# SCH_SPD-NFC.net
KiCad netlist of a schematic drawn in EasyEDA
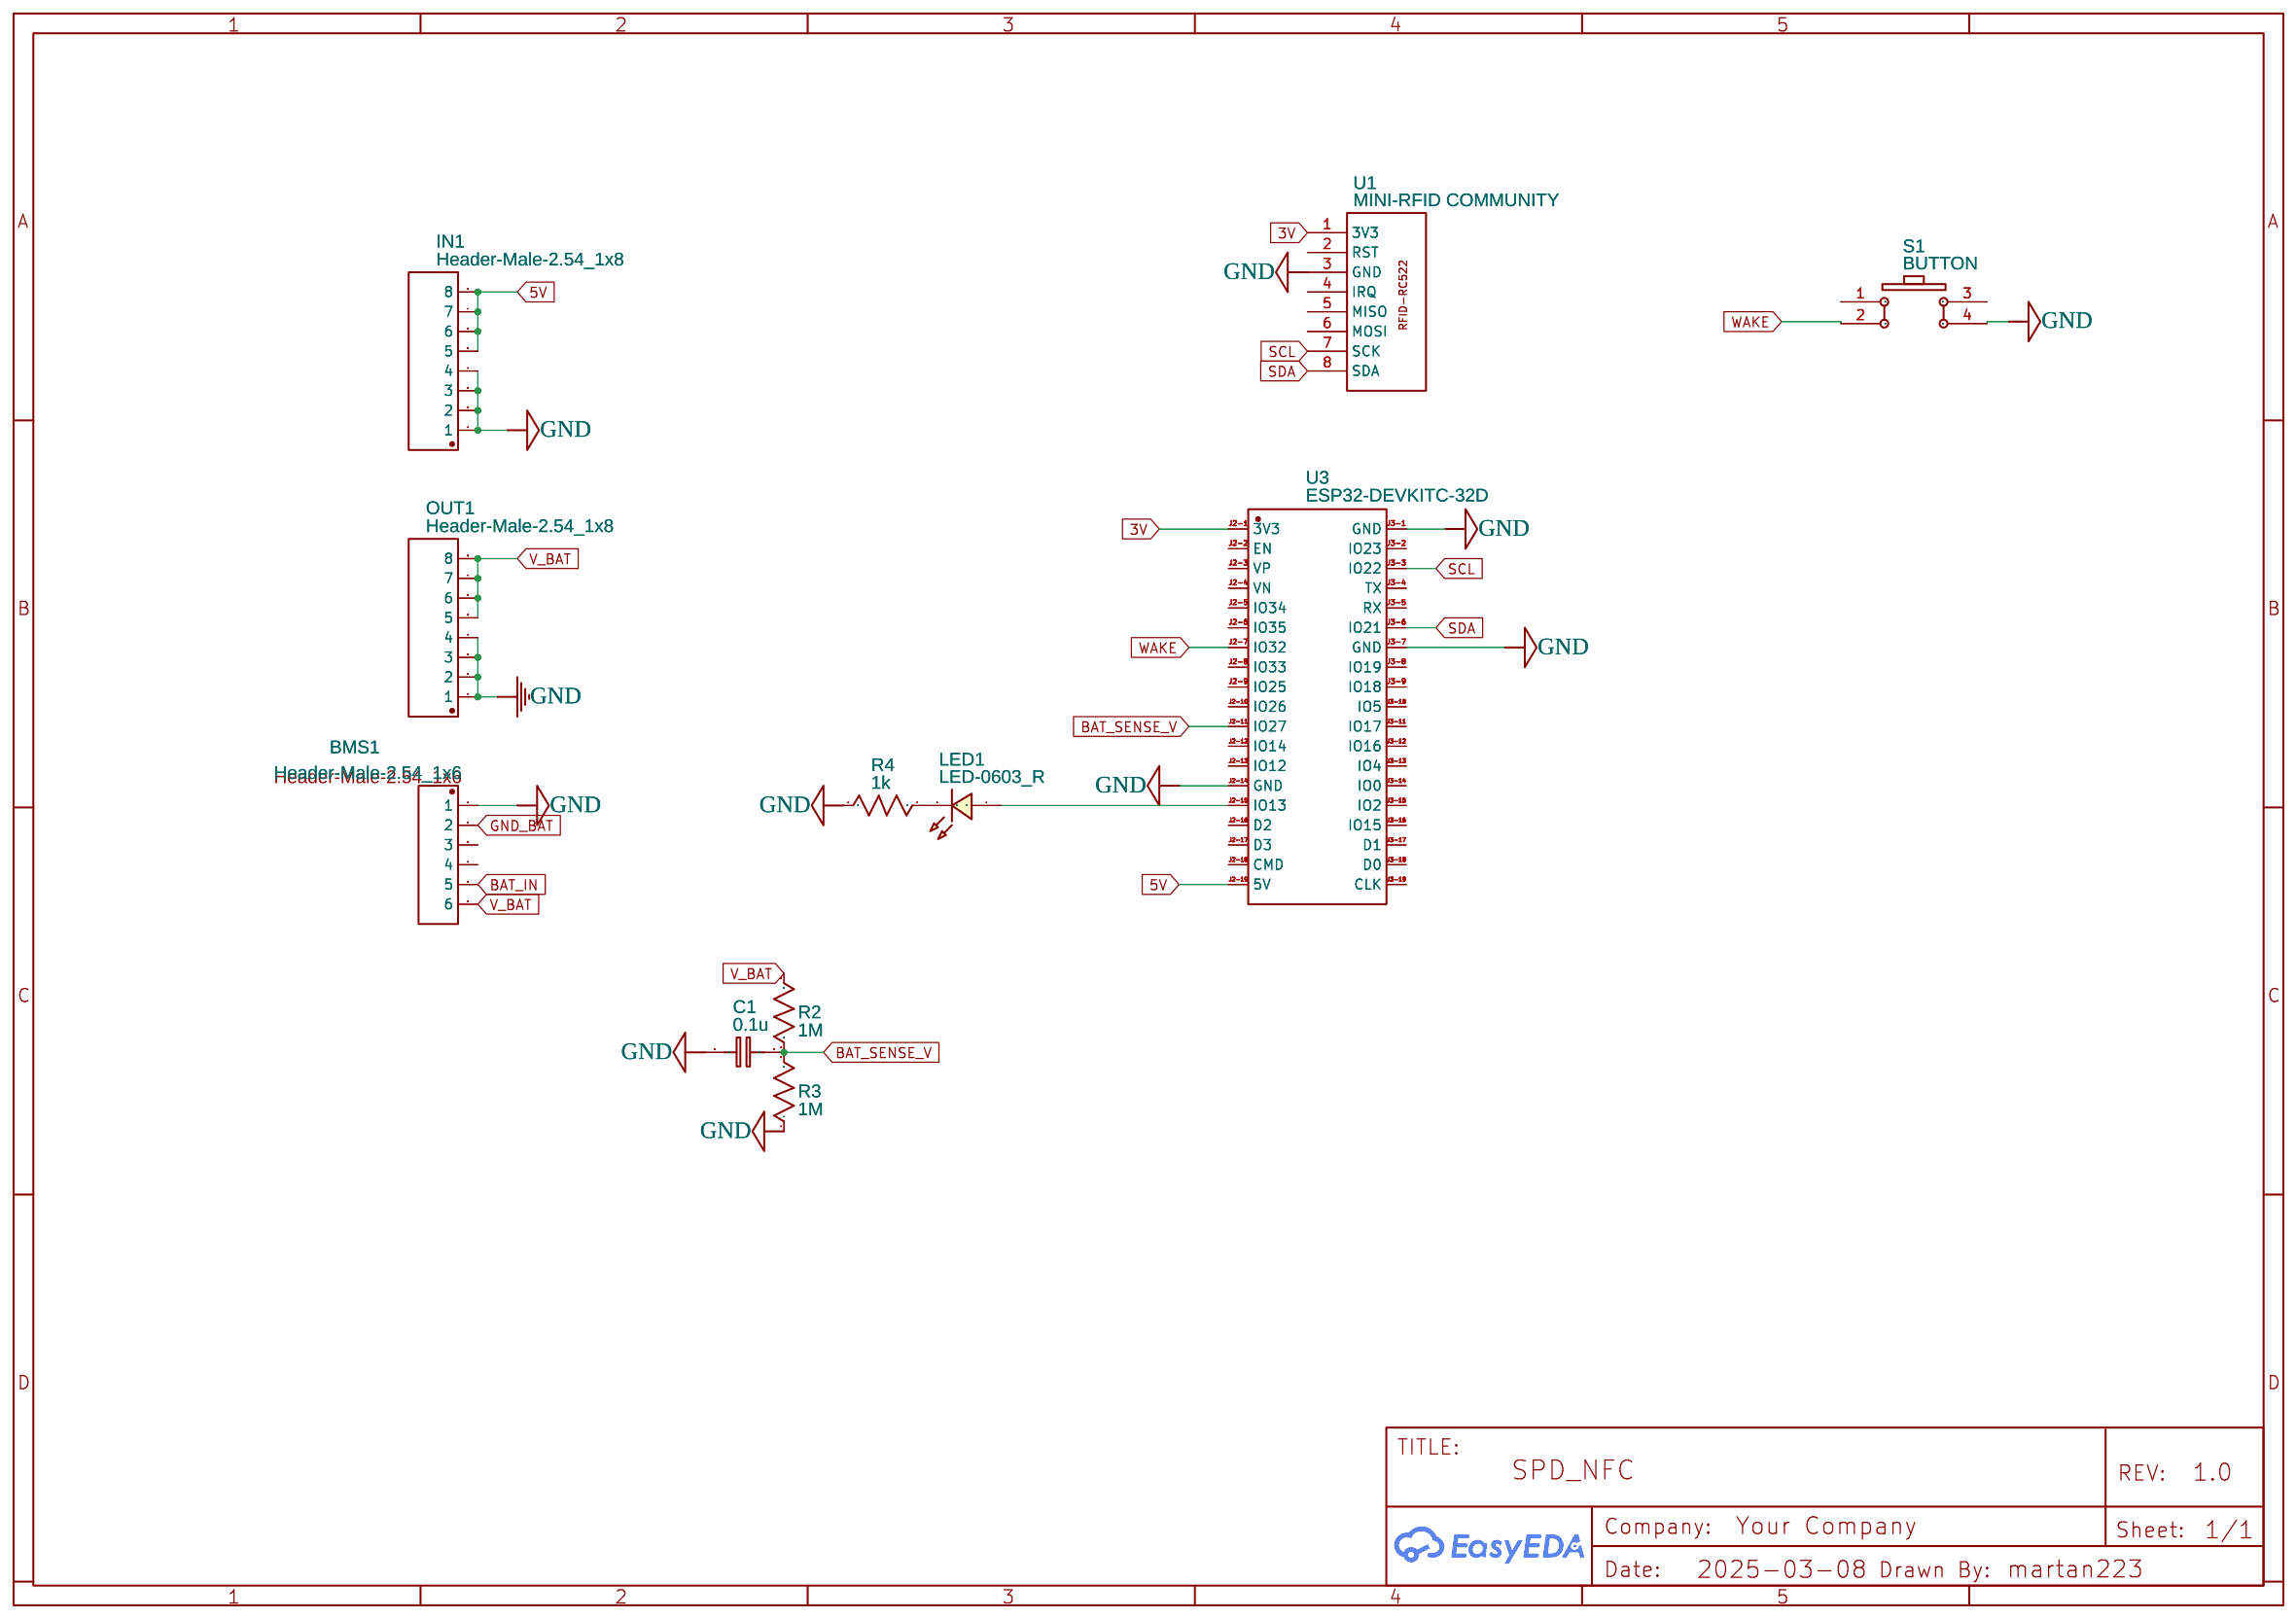
[diagram p0: schematic sheet]

(export (version "E")
  (design (tool "Eeschema 10.0.6"))
  (components
    (comp (ref "BMS1") (value "Header-Male-2.54_1x6") (libsource (lib "") (part "Header-Male-2.54_1x6")))
    (comp (ref "C1") (value "0.1u") (libsource (lib "") (part "C_0603_EU")))
    (comp (ref "IN1")
      (value "Header-Male-2.54_1x8")
      (fields (field (name "Manufacturer") "Ckmtw(灿科盟)"))
      (libsource (lib "") (part "Header-Male-2.54_1x8"))
    )
    (comp (ref "LED1")
      (value "LED-0603_R")
      (fields
        (field (name "Manufacturer Part") "19-217/R6C-AL1M2VY/3T")
        (field (name "Manufacturer") "EVERLIGHT(台湾亿光)")
      )
      (libsource (lib "") (part "LED-0603_R"))
    )
    (comp (ref "OUT1")
      (value "Header-Male-2.54_1x8")
      (fields (field (name "Manufacturer") "Ckmtw(灿科盟)"))
      (libsource (lib "") (part "Header-Male-2.54_1x8_1"))
    )
    (comp (ref "R2") (value "1M") (libsource (lib "") (part "R_0603_US_1")))
    (comp (ref "R3") (value "1M") (libsource (lib "") (part "R_0603_US_1")))
    (comp (ref "R4") (value "1k") (libsource (lib "") (part "R_0603_US")))
    (comp (ref "S1") (value "BUTTON") (libsource (lib "") (part "BUTTON")))
    (comp (ref "U1") (value "MINI-RFID COMMUNITY") (libsource (lib "") (part "MINI-RFID COMMUNITY")))
    (comp (ref "U3")
      (value "ESP32-DEVKITC-32D")
      (fields (field (name "Manufacturer") "ESPRESSIF(乐鑫)"))
      (libsource (lib "") (part "ESP32-DEVKITC-32D"))
    )
  )
  (nets
    (net (code "1") (name "3V") (class "Default")
      (node (ref "U1") (pin "1") (pinfunction "3V3_1") (pintype "unspecified"))
      (node (ref "U3") (pin "J2-1") (pinfunction "3V3_J2-1") (pintype "unspecified"))
    )
    (net (code "2") (name "5V") (class "Default")
      (node (ref "IN1") (pin "5") (pinfunction "5_5") (pintype "unspecified"))
      (node (ref "IN1") (pin "6") (pinfunction "6_6") (pintype "unspecified"))
      (node (ref "IN1") (pin "7") (pinfunction "7_7") (pintype "unspecified"))
      (node (ref "IN1") (pin "8") (pinfunction "8_8") (pintype "unspecified"))
      (node (ref "U3") (pin "J2-19") (pinfunction "5V_J2-19") (pintype "unspecified"))
    )
    (net (code "3") (name "BAT_IN") (class "Default")
      (node (ref "BMS1") (pin "5") (pinfunction "5_5") (pintype "unspecified"))
    )
    (net (code "4") (name "BAT_SENSE_V") (class "Default")
      (node (ref "C1") (pin "2") (pinfunction "2_2") (pintype "unspecified"))
      (node (ref "R2") (pin "1") (pinfunction "1_1") (pintype "unspecified"))
      (node (ref "R3") (pin "2") (pinfunction "2_2") (pintype "unspecified"))
      (node (ref "U3") (pin "J2-11") (pinfunction "IO27_J2-11") (pintype "unspecified"))
    )
    (net (code "5") (name "GND") (class "Default")
      (node (ref "BMS1") (pin "1") (pinfunction "1_1") (pintype "unspecified"))
      (node (ref "C1") (pin "1") (pinfunction "1_1") (pintype "unspecified"))
      (node (ref "IN1") (pin "1") (pinfunction "1_1") (pintype "unspecified"))
      (node (ref "IN1") (pin "2") (pinfunction "2_2") (pintype "unspecified"))
      (node (ref "IN1") (pin "3") (pinfunction "3_3") (pintype "unspecified"))
      (node (ref "IN1") (pin "4") (pinfunction "4_4") (pintype "unspecified"))
      (node (ref "OUT1") (pin "1") (pinfunction "1_1") (pintype "unspecified"))
      (node (ref "OUT1") (pin "2") (pinfunction "2_2") (pintype "unspecified"))
      (node (ref "OUT1") (pin "3") (pinfunction "3_3") (pintype "unspecified"))
      (node (ref "OUT1") (pin "4") (pinfunction "4_4") (pintype "unspecified"))
      (node (ref "R3") (pin "1") (pinfunction "1_1") (pintype "unspecified"))
      (node (ref "R4") (pin "1") (pinfunction "1_1") (pintype "unspecified"))
      (node (ref "S1") (pin "4") (pinfunction "3_4") (pintype "unspecified"))
      (node (ref "U1") (pin "3") (pinfunction "GND_3") (pintype "unspecified"))
      (node (ref "U3") (pin "J2-14") (pinfunction "GND_J2-14") (pintype "unspecified"))
      (node (ref "U3") (pin "J3-1") (pinfunction "GND_J3-1") (pintype "unspecified"))
      (node (ref "U3") (pin "J3-7") (pinfunction "GND_J3-7") (pintype "unspecified"))
    )
    (net (code "6") (name "GND_BAT") (class "Default")
      (node (ref "BMS1") (pin "2") (pinfunction "2_2") (pintype "unspecified"))
    )
    (net (code "7") (name "Net-(LED1-Pad2)") (class "Default")
      (node (ref "LED1") (pin "2") (pinfunction "2_2") (pintype "unspecified"))
      (node (ref "R4") (pin "2") (pinfunction "2_2") (pintype "unspecified"))
    )
    (net (code "8") (name "Net-(U3-IO13)") (class "Default")
      (node (ref "LED1") (pin "1") (pinfunction "1_1") (pintype "unspecified"))
      (node (ref "U3") (pin "J2-15") (pinfunction "IO13_J2-15") (pintype "unspecified"))
    )
    (net (code "9") (name "SCL") (class "Default")
      (node (ref "U1") (pin "7") (pinfunction "SCK_7") (pintype "unspecified"))
      (node (ref "U3") (pin "J3-3") (pinfunction "IO22_J3-3") (pintype "unspecified"))
    )
    (net (code "10") (name "SDA") (class "Default")
      (node (ref "U1") (pin "8") (pinfunction "SDA_8") (pintype "unspecified"))
      (node (ref "U3") (pin "J3-6") (pinfunction "IO21_J3-6") (pintype "unspecified"))
    )
    (net (code "11") (name "V_BAT") (class "Default")
      (node (ref "BMS1") (pin "6") (pinfunction "6_6") (pintype "unspecified"))
      (node (ref "OUT1") (pin "5") (pinfunction "5_5") (pintype "unspecified"))
      (node (ref "OUT1") (pin "6") (pinfunction "6_6") (pintype "unspecified"))
      (node (ref "OUT1") (pin "7") (pinfunction "7_7") (pintype "unspecified"))
      (node (ref "OUT1") (pin "8") (pinfunction "8_8") (pintype "unspecified"))
      (node (ref "R2") (pin "2") (pinfunction "2_2") (pintype "unspecified"))
    )
    (net (code "12") (name "WAKE") (class "Default")
      (node (ref "S1") (pin "2") (pinfunction "2_2") (pintype "unspecified"))
      (node (ref "U3") (pin "J2-7") (pinfunction "IO32_J2-7") (pintype "unspecified"))
    )
    (net (code "13") (name "unconnected-(BMS1-Pad3)") (class "Default")
      (node (ref "BMS1") (pin "3") (pinfunction "3_3") (pintype "unspecified"))
    )
    (net (code "14") (name "unconnected-(BMS1-Pad4)") (class "Default")
      (node (ref "BMS1") (pin "4") (pinfunction "4_4") (pintype "unspecified"))
    )
    (net (code "15") (name "unconnected-(S1-2-Pad1)") (class "Default")
      (node (ref "S1") (pin "1") (pinfunction "2_1") (pintype "unspecified"))
    )
    (net (code "16") (name "unconnected-(S1-Pad3)") (class "Default")
      (node (ref "S1") (pin "3") (pinfunction "3_3") (pintype "unspecified"))
    )
    (net (code "17") (name "unconnected-(U1-IRQ-Pad4)") (class "Default")
      (node (ref "U1") (pin "4") (pinfunction "IRQ_4") (pintype "unspecified"))
    )
    (net (code "18") (name "unconnected-(U1-MISO-Pad5)") (class "Default")
      (node (ref "U1") (pin "5") (pinfunction "MISO_5") (pintype "unspecified"))
    )
    (net (code "19") (name "unconnected-(U1-MOSI-Pad6)") (class "Default")
      (node (ref "U1") (pin "6") (pinfunction "MOSI_6") (pintype "unspecified"))
    )
    (net (code "20") (name "unconnected-(U1-RST-Pad2)") (class "Default")
      (node (ref "U1") (pin "2") (pinfunction "RST_2") (pintype "unspecified"))
    )
    (net (code "21") (name "unconnected-(U3-CLK-PadJ3-19)") (class "Default")
      (node (ref "U3") (pin "J3-19") (pinfunction "CLK_J3-19") (pintype "unspecified"))
    )
    (net (code "22") (name "unconnected-(U3-CMD-PadJ2-18)") (class "Default")
      (node (ref "U3") (pin "J2-18") (pinfunction "CMD_J2-18") (pintype "unspecified"))
    )
    (net (code "23") (name "unconnected-(U3-D0-PadJ3-18)") (class "Default")
      (node (ref "U3") (pin "J3-18") (pinfunction "D0_J3-18") (pintype "unspecified"))
    )
    (net (code "24") (name "unconnected-(U3-D1-PadJ3-17)") (class "Default")
      (node (ref "U3") (pin "J3-17") (pinfunction "D1_J3-17") (pintype "unspecified"))
    )
    (net (code "25") (name "unconnected-(U3-D2-PadJ2-16)") (class "Default")
      (node (ref "U3") (pin "J2-16") (pinfunction "D2_J2-16") (pintype "unspecified"))
    )
    (net (code "26") (name "unconnected-(U3-D3-PadJ2-17)") (class "Default")
      (node (ref "U3") (pin "J2-17") (pinfunction "D3_J2-17") (pintype "unspecified"))
    )
    (net (code "27") (name "unconnected-(U3-EN-PadJ2-2)") (class "Default")
      (node (ref "U3") (pin "J2-2") (pinfunction "EN_J2-2") (pintype "unspecified"))
    )
    (net (code "28") (name "unconnected-(U3-IO0-PadJ3-14)") (class "Default")
      (node (ref "U3") (pin "J3-14") (pinfunction "IO0_J3-14") (pintype "unspecified"))
    )
    (net (code "29") (name "unconnected-(U3-IO2-PadJ3-15)") (class "Default")
      (node (ref "U3") (pin "J3-15") (pinfunction "IO2_J3-15") (pintype "unspecified"))
    )
    (net (code "30") (name "unconnected-(U3-IO4-PadJ3-13)") (class "Default")
      (node (ref "U3") (pin "J3-13") (pinfunction "IO4_J3-13") (pintype "unspecified"))
    )
    (net (code "31") (name "unconnected-(U3-IO5-PadJ3-10)") (class "Default")
      (node (ref "U3") (pin "J3-10") (pinfunction "IO5_J3-10") (pintype "unspecified"))
    )
    (net (code "32") (name "unconnected-(U3-IO12-PadJ2-13)") (class "Default")
      (node (ref "U3") (pin "J2-13") (pinfunction "IO12_J2-13") (pintype "unspecified"))
    )
    (net (code "33") (name "unconnected-(U3-IO14-PadJ2-12)") (class "Default")
      (node (ref "U3") (pin "J2-12") (pinfunction "IO14_J2-12") (pintype "unspecified"))
    )
    (net (code "34") (name "unconnected-(U3-IO15-PadJ3-16)") (class "Default")
      (node (ref "U3") (pin "J3-16") (pinfunction "IO15_J3-16") (pintype "unspecified"))
    )
    (net (code "35") (name "unconnected-(U3-IO16-PadJ3-12)") (class "Default")
      (node (ref "U3") (pin "J3-12") (pinfunction "IO16_J3-12") (pintype "unspecified"))
    )
    (net (code "36") (name "unconnected-(U3-IO17-PadJ3-11)") (class "Default")
      (node (ref "U3") (pin "J3-11") (pinfunction "IO17_J3-11") (pintype "unspecified"))
    )
    (net (code "37") (name "unconnected-(U3-IO18-PadJ3-9)") (class "Default")
      (node (ref "U3") (pin "J3-9") (pinfunction "IO18_J3-9") (pintype "unspecified"))
    )
    (net (code "38") (name "unconnected-(U3-IO19-PadJ3-8)") (class "Default")
      (node (ref "U3") (pin "J3-8") (pinfunction "IO19_J3-8") (pintype "unspecified"))
    )
    (net (code "39") (name "unconnected-(U3-IO23-PadJ3-2)") (class "Default")
      (node (ref "U3") (pin "J3-2") (pinfunction "IO23_J3-2") (pintype "unspecified"))
    )
    (net (code "40") (name "unconnected-(U3-IO25-PadJ2-9)") (class "Default")
      (node (ref "U3") (pin "J2-9") (pinfunction "IO25_J2-9") (pintype "unspecified"))
    )
    (net (code "41") (name "unconnected-(U3-IO26-PadJ2-10)") (class "Default")
      (node (ref "U3") (pin "J2-10") (pinfunction "IO26_J2-10") (pintype "unspecified"))
    )
    (net (code "42") (name "unconnected-(U3-IO33-PadJ2-8)") (class "Default")
      (node (ref "U3") (pin "J2-8") (pinfunction "IO33_J2-8") (pintype "unspecified"))
    )
    (net (code "43") (name "unconnected-(U3-IO34-PadJ2-5)") (class "Default")
      (node (ref "U3") (pin "J2-5") (pinfunction "IO34_J2-5") (pintype "unspecified"))
    )
    (net (code "44") (name "unconnected-(U3-IO35-PadJ2-6)") (class "Default")
      (node (ref "U3") (pin "J2-6") (pinfunction "IO35_J2-6") (pintype "unspecified"))
    )
    (net (code "45") (name "unconnected-(U3-RX-PadJ3-5)") (class "Default")
      (node (ref "U3") (pin "J3-5") (pinfunction "RX_J3-5") (pintype "unspecified"))
    )
    (net (code "46") (name "unconnected-(U3-TX-PadJ3-4)") (class "Default")
      (node (ref "U3") (pin "J3-4") (pinfunction "TX_J3-4") (pintype "unspecified"))
    )
    (net (code "47") (name "unconnected-(U3-VN-PadJ2-4)") (class "Default")
      (node (ref "U3") (pin "J2-4") (pinfunction "VN_J2-4") (pintype "unspecified"))
    )
    (net (code "48") (name "unconnected-(U3-VP-PadJ2-3)") (class "Default")
      (node (ref "U3") (pin "J2-3") (pinfunction "VP_J2-3") (pintype "unspecified"))
    )
  )
)
